# Filter1.net
KiCad netlist of a schematic drawn in Altium Designer
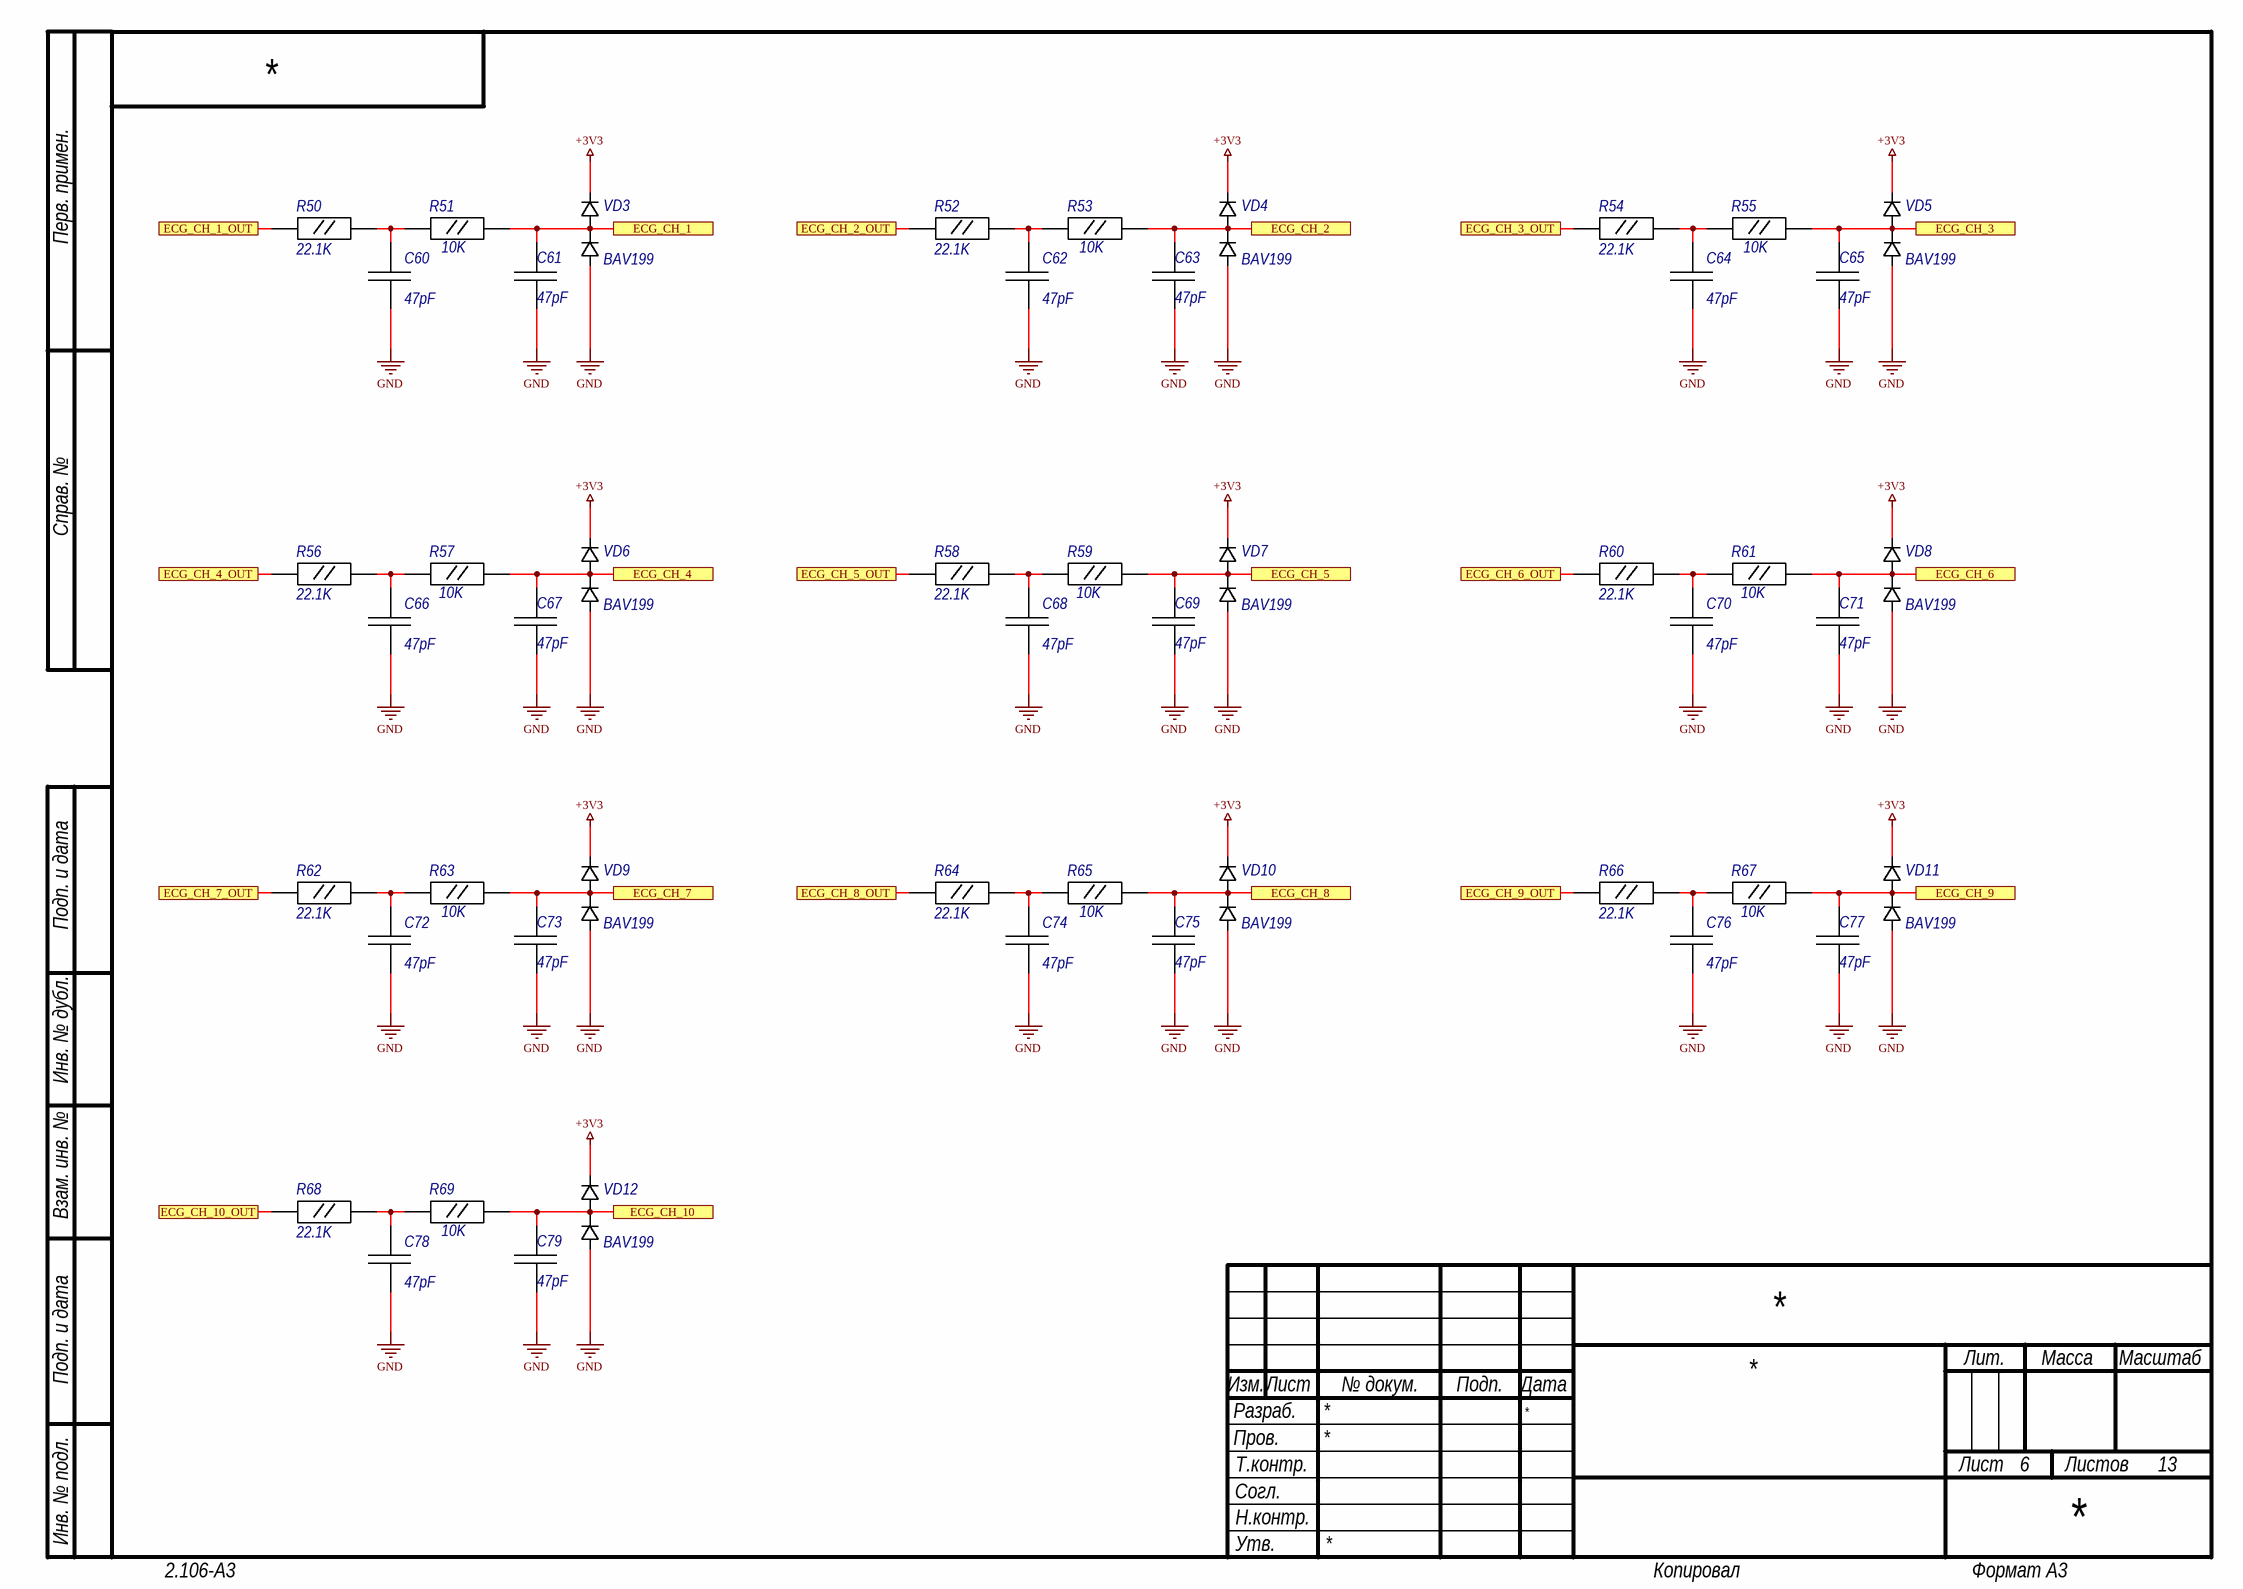
[diagram p0: Filter1.SchDoc]

(export (version "E")
  (design (tool "Eeschema 10.0.6"))
  (components
    (comp (ref "C60")
      (value "47pF")
      (footprint "C0603")
      (description "Ceramic Capacitor SMD")
      (libsource (lib "GOST") (part "CC_SMD_0603"))
    )
    (comp (ref "C61")
      (value "47pF")
      (footprint "C0603")
      (description "Ceramic Capacitor SMD")
      (libsource (lib "GOST") (part "CC_SMD_0603"))
    )
    (comp (ref "C62")
      (value "47pF")
      (footprint "C0603")
      (description "Ceramic Capacitor SMD")
      (libsource (lib "GOST") (part "CC_SMD_0603"))
    )
    (comp (ref "C63")
      (value "47pF")
      (footprint "C0603")
      (description "Ceramic Capacitor SMD")
      (libsource (lib "GOST") (part "CC_SMD_0603"))
    )
    (comp (ref "C64")
      (value "47pF")
      (footprint "C0603")
      (description "Ceramic Capacitor SMD")
      (libsource (lib "GOST") (part "CC_SMD_0603"))
    )
    (comp (ref "C65")
      (value "47pF")
      (footprint "C0603")
      (description "Ceramic Capacitor SMD")
      (libsource (lib "GOST") (part "CC_SMD_0603"))
    )
    (comp (ref "C66")
      (value "47pF")
      (footprint "C0603")
      (description "Ceramic Capacitor SMD")
      (libsource (lib "GOST") (part "CC_SMD_0603"))
    )
    (comp (ref "C67")
      (value "47pF")
      (footprint "C0603")
      (description "Ceramic Capacitor SMD")
      (libsource (lib "GOST") (part "CC_SMD_0603"))
    )
    (comp (ref "C68")
      (value "47pF")
      (footprint "C0603")
      (description "Ceramic Capacitor SMD")
      (libsource (lib "GOST") (part "CC_SMD_0603"))
    )
    (comp (ref "C69")
      (value "47pF")
      (footprint "C0603")
      (description "Ceramic Capacitor SMD")
      (libsource (lib "GOST") (part "CC_SMD_0603"))
    )
    (comp (ref "C70")
      (value "47pF")
      (footprint "C0603")
      (description "Ceramic Capacitor SMD")
      (libsource (lib "GOST") (part "CC_SMD_0603"))
    )
    (comp (ref "C71")
      (value "47pF")
      (footprint "C0603")
      (description "Ceramic Capacitor SMD")
      (libsource (lib "GOST") (part "CC_SMD_0603"))
    )
    (comp (ref "C72")
      (value "47pF")
      (footprint "C0603")
      (description "Ceramic Capacitor SMD")
      (libsource (lib "GOST") (part "CC_SMD_0603"))
    )
    (comp (ref "C73")
      (value "47pF")
      (footprint "C0603")
      (description "Ceramic Capacitor SMD")
      (libsource (lib "GOST") (part "CC_SMD_0603"))
    )
    (comp (ref "C74")
      (value "47pF")
      (footprint "C0603")
      (description "Ceramic Capacitor SMD")
      (libsource (lib "GOST") (part "CC_SMD_0603"))
    )
    (comp (ref "C75")
      (value "47pF")
      (footprint "C0603")
      (description "Ceramic Capacitor SMD")
      (libsource (lib "GOST") (part "CC_SMD_0603"))
    )
    (comp (ref "C76")
      (value "47pF")
      (footprint "C0603")
      (description "Ceramic Capacitor SMD")
      (libsource (lib "GOST") (part "CC_SMD_0603"))
    )
    (comp (ref "C77")
      (value "47pF")
      (footprint "C0603")
      (description "Ceramic Capacitor SMD")
      (libsource (lib "GOST") (part "CC_SMD_0603"))
    )
    (comp (ref "C78")
      (value "47pF")
      (footprint "C0603")
      (description "Ceramic Capacitor SMD")
      (libsource (lib "GOST") (part "CC_SMD_0603"))
    )
    (comp (ref "C79")
      (value "47pF")
      (footprint "C0603")
      (description "Ceramic Capacitor SMD")
      (libsource (lib "GOST") (part "CC_SMD_0603"))
    )
    (comp (ref "R50")
      (value "22.1K")
      (footprint "R0603")
      (description "Resistor SMD")
      (libsource (lib "GOST") (part "R0603"))
    )
    (comp (ref "R51")
      (value "10K")
      (footprint "R0603")
      (description "Resistor SMD")
      (libsource (lib "GOST") (part "R0603"))
    )
    (comp (ref "R52")
      (value "22.1K")
      (footprint "R0603")
      (description "Resistor SMD")
      (libsource (lib "GOST") (part "R0603"))
    )
    (comp (ref "R53")
      (value "10K")
      (footprint "R0603")
      (description "Resistor SMD")
      (libsource (lib "GOST") (part "R0603"))
    )
    (comp (ref "R54")
      (value "22.1K")
      (footprint "R0603")
      (description "Resistor SMD")
      (libsource (lib "GOST") (part "R0603"))
    )
    (comp (ref "R55")
      (value "10K")
      (footprint "R0603")
      (description "Resistor SMD")
      (libsource (lib "GOST") (part "R0603"))
    )
    (comp (ref "R56")
      (value "22.1K")
      (footprint "R0603")
      (description "Resistor SMD")
      (libsource (lib "GOST") (part "R0603"))
    )
    (comp (ref "R57")
      (value "10K")
      (footprint "R0603")
      (description "Resistor SMD")
      (libsource (lib "GOST") (part "R0603"))
    )
    (comp (ref "R58")
      (value "22.1K")
      (footprint "R0603")
      (description "Resistor SMD")
      (libsource (lib "GOST") (part "R0603"))
    )
    (comp (ref "R59")
      (value "10K")
      (footprint "R0603")
      (description "Resistor SMD")
      (libsource (lib "GOST") (part "R0603"))
    )
    (comp (ref "R60")
      (value "22.1K")
      (footprint "R0603")
      (description "Resistor SMD")
      (libsource (lib "GOST") (part "R0603"))
    )
    (comp (ref "R61")
      (value "10K")
      (footprint "R0603")
      (description "Resistor SMD")
      (libsource (lib "GOST") (part "R0603"))
    )
    (comp (ref "R62")
      (value "22.1K")
      (footprint "R0603")
      (description "Resistor SMD")
      (libsource (lib "GOST") (part "R0603"))
    )
    (comp (ref "R63")
      (value "10K")
      (footprint "R0603")
      (description "Resistor SMD")
      (libsource (lib "GOST") (part "R0603"))
    )
    (comp (ref "R64")
      (value "22.1K")
      (footprint "R0603")
      (description "Resistor SMD")
      (libsource (lib "GOST") (part "R0603"))
    )
    (comp (ref "R65")
      (value "10K")
      (footprint "R0603")
      (description "Resistor SMD")
      (libsource (lib "GOST") (part "R0603"))
    )
    (comp (ref "R66")
      (value "22.1K")
      (footprint "R0603")
      (description "Resistor SMD")
      (libsource (lib "GOST") (part "R0603"))
    )
    (comp (ref "R67")
      (value "10K")
      (footprint "R0603")
      (description "Resistor SMD")
      (libsource (lib "GOST") (part "R0603"))
    )
    (comp (ref "R68")
      (value "22.1K")
      (footprint "R0603")
      (description "Resistor SMD")
      (libsource (lib "GOST") (part "R0603"))
    )
    (comp (ref "R69")
      (value "10K")
      (footprint "R0603")
      (description "Resistor SMD")
      (libsource (lib "GOST") (part "R0603"))
    )
    (comp (ref "VD3")
      (value "BAV199")
      (footprint "SOT23")
      (description "Diod Schottky")
      (fields (field (name "MANUFACTURER PART NUMBER 1") "BAV199"))
      (libsource (lib "GOST") (part "DIODE_BAV199"))
    )
    (comp (ref "VD4")
      (value "BAV199")
      (footprint "SOT23")
      (description "Diod Schottky")
      (fields (field (name "MANUFACTURER PART NUMBER 1") "BAV199"))
      (libsource (lib "GOST") (part "DIODE_BAV199"))
    )
    (comp (ref "VD5")
      (value "BAV199")
      (footprint "SOT23")
      (description "Diod Schottky")
      (fields (field (name "MANUFACTURER PART NUMBER 1") "BAV199"))
      (libsource (lib "GOST") (part "DIODE_BAV199"))
    )
    (comp (ref "VD6")
      (value "BAV199")
      (footprint "SOT23")
      (description "Diod Schottky")
      (fields (field (name "MANUFACTURER PART NUMBER 1") "BAV199"))
      (libsource (lib "GOST") (part "DIODE_BAV199"))
    )
    (comp (ref "VD7")
      (value "BAV199")
      (footprint "SOT23")
      (description "Diod Schottky")
      (fields (field (name "MANUFACTURER PART NUMBER 1") "BAV199"))
      (libsource (lib "GOST") (part "DIODE_BAV199"))
    )
    (comp (ref "VD8")
      (value "BAV199")
      (footprint "SOT23")
      (description "Diod Schottky")
      (fields (field (name "MANUFACTURER PART NUMBER 1") "BAV199"))
      (libsource (lib "GOST") (part "DIODE_BAV199"))
    )
    (comp (ref "VD9")
      (value "BAV199")
      (footprint "SOT23")
      (description "Diod Schottky")
      (fields (field (name "MANUFACTURER PART NUMBER 1") "BAV199"))
      (libsource (lib "GOST") (part "DIODE_BAV199"))
    )
    (comp (ref "VD10")
      (value "BAV199")
      (footprint "SOT23")
      (description "Diod Schottky")
      (fields (field (name "MANUFACTURER PART NUMBER 1") "BAV199"))
      (libsource (lib "GOST") (part "DIODE_BAV199"))
    )
    (comp (ref "VD11")
      (value "BAV199")
      (footprint "SOT23")
      (description "Diod Schottky")
      (fields (field (name "MANUFACTURER PART NUMBER 1") "BAV199"))
      (libsource (lib "GOST") (part "DIODE_BAV199"))
    )
    (comp (ref "VD12")
      (value "BAV199")
      (footprint "SOT23")
      (description "Diod Schottky")
      (fields (field (name "MANUFACTURER PART NUMBER 1") "BAV199"))
      (libsource (lib "GOST") (part "DIODE_BAV199"))
    )
  )
  (nets
    (net (code "1") (name "+3V3") (class "Default")
      (node (ref "VD10") (pin "2") (pinfunction "2_2") (pintype "passive"))
      (node (ref "VD11") (pin "2") (pinfunction "2_2") (pintype "passive"))
      (node (ref "VD12") (pin "2") (pinfunction "2_2") (pintype "passive"))
      (node (ref "VD3") (pin "2") (pinfunction "2_2") (pintype "passive"))
      (node (ref "VD4") (pin "2") (pinfunction "2_2") (pintype "passive"))
      (node (ref "VD5") (pin "2") (pinfunction "2_2") (pintype "passive"))
      (node (ref "VD6") (pin "2") (pinfunction "2_2") (pintype "passive"))
      (node (ref "VD7") (pin "2") (pinfunction "2_2") (pintype "passive"))
      (node (ref "VD8") (pin "2") (pinfunction "2_2") (pintype "passive"))
      (node (ref "VD9") (pin "2") (pinfunction "2_2") (pintype "passive"))
    )
    (net (code "2") (name "/ECG_CH_1") (class "Default")
      (node (ref "C61") (pin "2") (pinfunction "2_2") (pintype "passive"))
      (node (ref "R51") (pin "2") (pinfunction "2_2") (pintype "passive"))
      (node (ref "VD3") (pin "3") (pinfunction "3_3") (pintype "passive"))
    )
    (net (code "3") (name "/ECG_CH_1_OUT") (class "Default")
      (node (ref "R50") (pin "1") (pinfunction "1_1") (pintype "passive"))
    )
    (net (code "4") (name "/ECG_CH_2") (class "Default")
      (node (ref "C63") (pin "2") (pinfunction "2_2") (pintype "passive"))
      (node (ref "R53") (pin "2") (pinfunction "2_2") (pintype "passive"))
      (node (ref "VD4") (pin "3") (pinfunction "3_3") (pintype "passive"))
    )
    (net (code "5") (name "/ECG_CH_2_OUT") (class "Default")
      (node (ref "R52") (pin "1") (pinfunction "1_1") (pintype "passive"))
    )
    (net (code "6") (name "/ECG_CH_3") (class "Default")
      (node (ref "C65") (pin "2") (pinfunction "2_2") (pintype "passive"))
      (node (ref "R55") (pin "2") (pinfunction "2_2") (pintype "passive"))
      (node (ref "VD5") (pin "3") (pinfunction "3_3") (pintype "passive"))
    )
    (net (code "7") (name "/ECG_CH_3_OUT") (class "Default")
      (node (ref "R54") (pin "1") (pinfunction "1_1") (pintype "passive"))
    )
    (net (code "8") (name "/ECG_CH_4") (class "Default")
      (node (ref "C67") (pin "2") (pinfunction "2_2") (pintype "passive"))
      (node (ref "R57") (pin "2") (pinfunction "2_2") (pintype "passive"))
      (node (ref "VD6") (pin "3") (pinfunction "3_3") (pintype "passive"))
    )
    (net (code "9") (name "/ECG_CH_4_OUT") (class "Default")
      (node (ref "R56") (pin "1") (pinfunction "1_1") (pintype "passive"))
    )
    (net (code "10") (name "/ECG_CH_5") (class "Default")
      (node (ref "C69") (pin "2") (pinfunction "2_2") (pintype "passive"))
      (node (ref "R59") (pin "2") (pinfunction "2_2") (pintype "passive"))
      (node (ref "VD7") (pin "3") (pinfunction "3_3") (pintype "passive"))
    )
    (net (code "11") (name "/ECG_CH_5_OUT") (class "Default")
      (node (ref "R58") (pin "1") (pinfunction "1_1") (pintype "passive"))
    )
    (net (code "12") (name "/ECG_CH_6") (class "Default")
      (node (ref "C71") (pin "2") (pinfunction "2_2") (pintype "passive"))
      (node (ref "R61") (pin "2") (pinfunction "2_2") (pintype "passive"))
      (node (ref "VD8") (pin "3") (pinfunction "3_3") (pintype "passive"))
    )
    (net (code "13") (name "/ECG_CH_6_OUT") (class "Default")
      (node (ref "R60") (pin "1") (pinfunction "1_1") (pintype "passive"))
    )
    (net (code "14") (name "/ECG_CH_7") (class "Default")
      (node (ref "C73") (pin "2") (pinfunction "2_2") (pintype "passive"))
      (node (ref "R63") (pin "2") (pinfunction "2_2") (pintype "passive"))
      (node (ref "VD9") (pin "3") (pinfunction "3_3") (pintype "passive"))
    )
    (net (code "15") (name "/ECG_CH_7_OUT") (class "Default")
      (node (ref "R62") (pin "1") (pinfunction "1_1") (pintype "passive"))
    )
    (net (code "16") (name "/ECG_CH_8") (class "Default")
      (node (ref "C75") (pin "2") (pinfunction "2_2") (pintype "passive"))
      (node (ref "R65") (pin "2") (pinfunction "2_2") (pintype "passive"))
      (node (ref "VD10") (pin "3") (pinfunction "3_3") (pintype "passive"))
    )
    (net (code "17") (name "/ECG_CH_8_OUT") (class "Default")
      (node (ref "R64") (pin "1") (pinfunction "1_1") (pintype "passive"))
    )
    (net (code "18") (name "/ECG_CH_9") (class "Default")
      (node (ref "C77") (pin "2") (pinfunction "2_2") (pintype "passive"))
      (node (ref "R67") (pin "2") (pinfunction "2_2") (pintype "passive"))
      (node (ref "VD11") (pin "3") (pinfunction "3_3") (pintype "passive"))
    )
    (net (code "19") (name "/ECG_CH_9_OUT") (class "Default")
      (node (ref "R66") (pin "1") (pinfunction "1_1") (pintype "passive"))
    )
    (net (code "20") (name "/ECG_CH_10") (class "Default")
      (node (ref "C79") (pin "2") (pinfunction "2_2") (pintype "passive"))
      (node (ref "R69") (pin "2") (pinfunction "2_2") (pintype "passive"))
      (node (ref "VD12") (pin "3") (pinfunction "3_3") (pintype "passive"))
    )
    (net (code "21") (name "/ECG_CH_10_OUT") (class "Default")
      (node (ref "R68") (pin "1") (pinfunction "1_1") (pintype "passive"))
    )
    (net (code "22") (name "GND") (class "Default")
      (node (ref "C60") (pin "1") (pinfunction "1_1") (pintype "passive"))
      (node (ref "C61") (pin "1") (pinfunction "1_1") (pintype "passive"))
      (node (ref "C62") (pin "1") (pinfunction "1_1") (pintype "passive"))
      (node (ref "C63") (pin "1") (pinfunction "1_1") (pintype "passive"))
      (node (ref "C64") (pin "1") (pinfunction "1_1") (pintype "passive"))
      (node (ref "C65") (pin "1") (pinfunction "1_1") (pintype "passive"))
      (node (ref "C66") (pin "1") (pinfunction "1_1") (pintype "passive"))
      (node (ref "C67") (pin "1") (pinfunction "1_1") (pintype "passive"))
      (node (ref "C68") (pin "1") (pinfunction "1_1") (pintype "passive"))
      (node (ref "C69") (pin "1") (pinfunction "1_1") (pintype "passive"))
      (node (ref "C70") (pin "1") (pinfunction "1_1") (pintype "passive"))
      (node (ref "C71") (pin "1") (pinfunction "1_1") (pintype "passive"))
      (node (ref "C72") (pin "1") (pinfunction "1_1") (pintype "passive"))
      (node (ref "C73") (pin "1") (pinfunction "1_1") (pintype "passive"))
      (node (ref "C74") (pin "1") (pinfunction "1_1") (pintype "passive"))
      (node (ref "C75") (pin "1") (pinfunction "1_1") (pintype "passive"))
      (node (ref "C76") (pin "1") (pinfunction "1_1") (pintype "passive"))
      (node (ref "C77") (pin "1") (pinfunction "1_1") (pintype "passive"))
      (node (ref "C78") (pin "1") (pinfunction "1_1") (pintype "passive"))
      (node (ref "C79") (pin "1") (pinfunction "1_1") (pintype "passive"))
      (node (ref "VD10") (pin "1") (pinfunction "1_1") (pintype "passive"))
      (node (ref "VD11") (pin "1") (pinfunction "1_1") (pintype "passive"))
      (node (ref "VD12") (pin "1") (pinfunction "1_1") (pintype "passive"))
      (node (ref "VD3") (pin "1") (pinfunction "1_1") (pintype "passive"))
      (node (ref "VD4") (pin "1") (pinfunction "1_1") (pintype "passive"))
      (node (ref "VD5") (pin "1") (pinfunction "1_1") (pintype "passive"))
      (node (ref "VD6") (pin "1") (pinfunction "1_1") (pintype "passive"))
      (node (ref "VD7") (pin "1") (pinfunction "1_1") (pintype "passive"))
      (node (ref "VD8") (pin "1") (pinfunction "1_1") (pintype "passive"))
      (node (ref "VD9") (pin "1") (pinfunction "1_1") (pintype "passive"))
    )
    (net (code "23") (name "Net-(C60-Pad2)") (class "Default")
      (node (ref "C60") (pin "2") (pinfunction "2_2") (pintype "passive"))
      (node (ref "R50") (pin "2") (pinfunction "2_2") (pintype "passive"))
      (node (ref "R51") (pin "1") (pinfunction "1_1") (pintype "passive"))
    )
    (net (code "24") (name "Net-(C62-Pad2)") (class "Default")
      (node (ref "C62") (pin "2") (pinfunction "2_2") (pintype "passive"))
      (node (ref "R52") (pin "2") (pinfunction "2_2") (pintype "passive"))
      (node (ref "R53") (pin "1") (pinfunction "1_1") (pintype "passive"))
    )
    (net (code "25") (name "Net-(C64-Pad2)") (class "Default")
      (node (ref "C64") (pin "2") (pinfunction "2_2") (pintype "passive"))
      (node (ref "R54") (pin "2") (pinfunction "2_2") (pintype "passive"))
      (node (ref "R55") (pin "1") (pinfunction "1_1") (pintype "passive"))
    )
    (net (code "26") (name "Net-(C66-Pad2)") (class "Default")
      (node (ref "C66") (pin "2") (pinfunction "2_2") (pintype "passive"))
      (node (ref "R56") (pin "2") (pinfunction "2_2") (pintype "passive"))
      (node (ref "R57") (pin "1") (pinfunction "1_1") (pintype "passive"))
    )
    (net (code "27") (name "Net-(C68-Pad2)") (class "Default")
      (node (ref "C68") (pin "2") (pinfunction "2_2") (pintype "passive"))
      (node (ref "R58") (pin "2") (pinfunction "2_2") (pintype "passive"))
      (node (ref "R59") (pin "1") (pinfunction "1_1") (pintype "passive"))
    )
    (net (code "28") (name "Net-(C70-Pad2)") (class "Default")
      (node (ref "C70") (pin "2") (pinfunction "2_2") (pintype "passive"))
      (node (ref "R60") (pin "2") (pinfunction "2_2") (pintype "passive"))
      (node (ref "R61") (pin "1") (pinfunction "1_1") (pintype "passive"))
    )
    (net (code "29") (name "Net-(C72-Pad2)") (class "Default")
      (node (ref "C72") (pin "2") (pinfunction "2_2") (pintype "passive"))
      (node (ref "R62") (pin "2") (pinfunction "2_2") (pintype "passive"))
      (node (ref "R63") (pin "1") (pinfunction "1_1") (pintype "passive"))
    )
    (net (code "30") (name "Net-(C74-Pad2)") (class "Default")
      (node (ref "C74") (pin "2") (pinfunction "2_2") (pintype "passive"))
      (node (ref "R64") (pin "2") (pinfunction "2_2") (pintype "passive"))
      (node (ref "R65") (pin "1") (pinfunction "1_1") (pintype "passive"))
    )
    (net (code "31") (name "Net-(C76-Pad2)") (class "Default")
      (node (ref "C76") (pin "2") (pinfunction "2_2") (pintype "passive"))
      (node (ref "R66") (pin "2") (pinfunction "2_2") (pintype "passive"))
      (node (ref "R67") (pin "1") (pinfunction "1_1") (pintype "passive"))
    )
    (net (code "32") (name "Net-(C78-Pad2)") (class "Default")
      (node (ref "C78") (pin "2") (pinfunction "2_2") (pintype "passive"))
      (node (ref "R68") (pin "2") (pinfunction "2_2") (pintype "passive"))
      (node (ref "R69") (pin "1") (pinfunction "1_1") (pintype "passive"))
    )
  )
)
